# MRCS-8xDPDT-Relay_v1_1.net
KiCad netlist of a schematic drawn in EAGLE
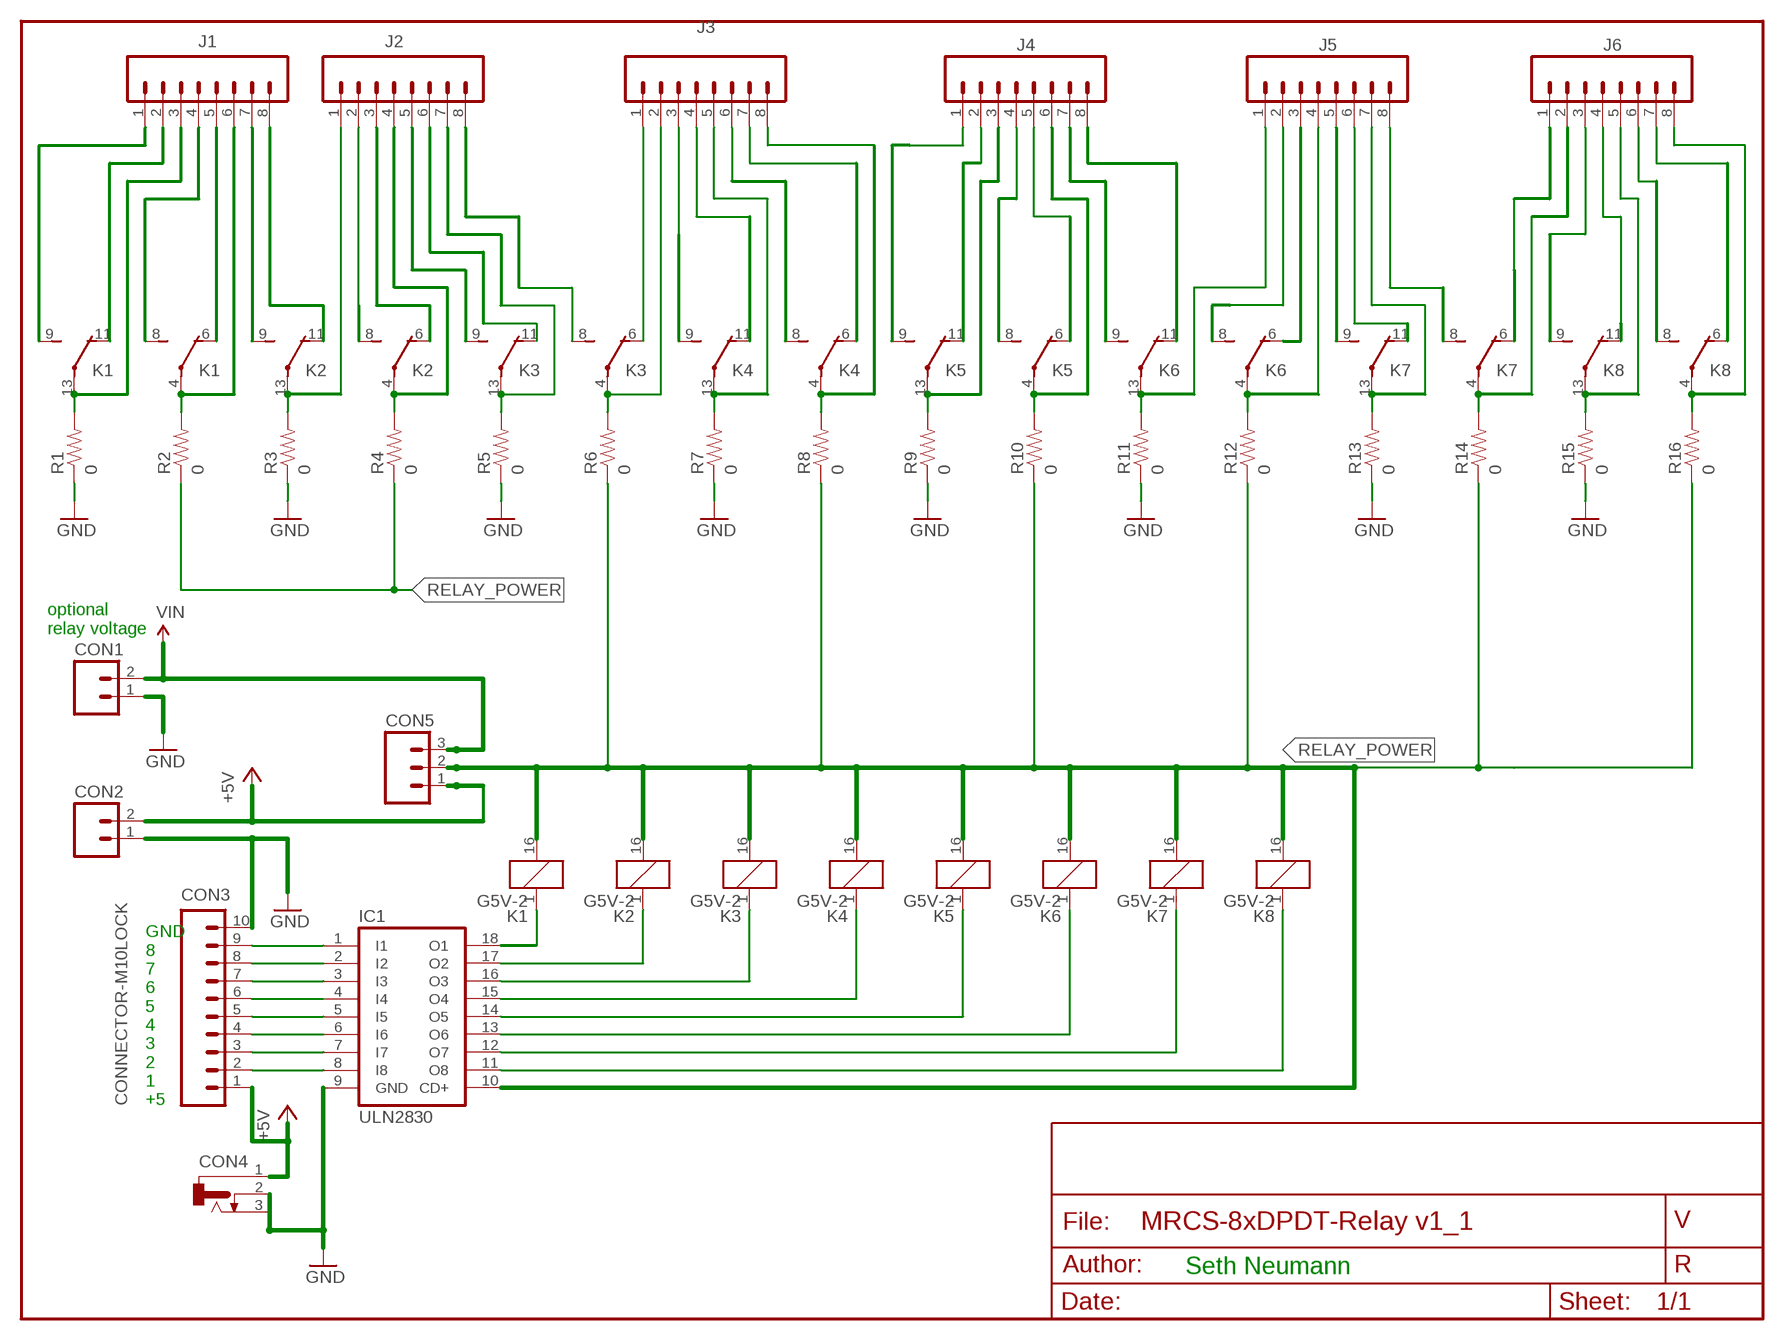
[diagram p0: schematic, sheet 1]

(export (version "E")
  (design (tool "Eeschema 10.0.6"))
  (components
    (comp (ref "CON1")
      (value "CONNECTOR-M023.5MM-LOCK")
      (footprint "eagle-import:SCREWTERMINAL-3.5MM-2_LOCK")
      (libsource (lib "eagle-import") (part "CONNECTOR-M023.5MM-LOCK"))
    )
    (comp (ref "CON2")
      (value "CONNECTOR-M023.5MM-LOCK")
      (footprint "eagle-import:SCREWTERMINAL-3.5MM-2_LOCK")
      (libsource (lib "eagle-import") (part "CONNECTOR-M023.5MM-LOCK"))
    )
    (comp (ref "CON3")
      (value "CONNECTOR-M10LOCK")
      (footprint "eagle-import:1X10_LOCK")
      (libsource (lib "eagle-import") (part "CONNECTOR-M10LOCK"))
    )
    (comp (ref "CON4")
      (value "CONNECTOR-DC-POWER-RA")
      (footprint "eagle-import:DCJ0202")
      (libsource (lib "eagle-import") (part "CONNECTOR-DC-POWER-RA"))
    )
    (comp (ref "CON5")
      (value "CONNECTOR-M03MOLEX-254-LOCK")
      (footprint "eagle-import:MOLEX-1X3_LOCK")
      (libsource (lib "eagle-import") (part "CONNECTOR-M03MOLEX-254-LOCK"))
    )
    (comp (ref "IC1")
      (value "ULN2830")
      (footprint "eagle-import:DIL18")
      (libsource (lib "eagle-import") (part "ULN2803A"))
    )
    (comp (ref "J1")
      (value "CONNECTOR-M08LOCK")
      (footprint "eagle-import:1X08_LOCK")
      (libsource (lib "eagle-import") (part "CONNECTOR-M08LOCK"))
    )
    (comp (ref "J2")
      (value "CONNECTOR-M08LOCK")
      (footprint "eagle-import:1X08_LOCK")
      (libsource (lib "eagle-import") (part "CONNECTOR-M08LOCK"))
    )
    (comp (ref "J3")
      (value "CONNECTOR-M08LOCK")
      (footprint "eagle-import:1X08_LOCK")
      (libsource (lib "eagle-import") (part "CONNECTOR-M08LOCK"))
    )
    (comp (ref "J4")
      (value "CONNECTOR-M08LOCK")
      (footprint "eagle-import:1X08_LOCK")
      (libsource (lib "eagle-import") (part "CONNECTOR-M08LOCK"))
    )
    (comp (ref "J5")
      (value "CONNECTOR-M08LOCK")
      (footprint "eagle-import:1X08_LOCK")
      (libsource (lib "eagle-import") (part "CONNECTOR-M08LOCK"))
    )
    (comp (ref "J6")
      (value "CONNECTOR-M08LOCK")
      (footprint "eagle-import:1X08_LOCK")
      (libsource (lib "eagle-import") (part "CONNECTOR-M08LOCK"))
    )
    (comp (ref "K1")
      (value "G5V-2")
      (footprint "eagle-import:G5V-2")
      (fields (field (name "MPN") "G5V-2 5DC"))
      (libsource (lib "eagle-import") (part "G5V-2"))
    )
    (comp (ref "K2")
      (value "G5V-2")
      (footprint "eagle-import:G5V-2")
      (fields (field (name "MPN") "G5V-2 5DC"))
      (libsource (lib "eagle-import") (part "G5V-2"))
    )
    (comp (ref "K3")
      (value "G5V-2")
      (footprint "eagle-import:G5V-2")
      (fields (field (name "MPN") "G5V-2 5DC"))
      (libsource (lib "eagle-import") (part "G5V-2"))
    )
    (comp (ref "K4")
      (value "G5V-2")
      (footprint "eagle-import:G5V-2")
      (fields (field (name "MPN") "G5V-2 5DC"))
      (libsource (lib "eagle-import") (part "G5V-2"))
    )
    (comp (ref "K5")
      (value "G5V-2")
      (footprint "eagle-import:G5V-2")
      (fields (field (name "MPN") "G5V-2 5DC"))
      (libsource (lib "eagle-import") (part "G5V-2"))
    )
    (comp (ref "K6")
      (value "G5V-2")
      (footprint "eagle-import:G5V-2")
      (fields (field (name "MPN") "G5V-2 5DC"))
      (libsource (lib "eagle-import") (part "G5V-2"))
    )
    (comp (ref "K7")
      (value "G5V-2")
      (footprint "eagle-import:G5V-2")
      (fields (field (name "MPN") "G5V-2 5DC"))
      (libsource (lib "eagle-import") (part "G5V-2"))
    )
    (comp (ref "K8")
      (value "G5V-2")
      (footprint "eagle-import:G5V-2")
      (fields (field (name "MPN") "G5V-2 5DC"))
      (libsource (lib "eagle-import") (part "G5V-2"))
    )
    (comp (ref "R1")
      (value "0")
      (footprint "eagle-import:CUT-R")
      (libsource (lib "eagle-import") (part "RPTH-R0"))
    )
    (comp (ref "R2")
      (value "0")
      (footprint "eagle-import:CUT-R")
      (libsource (lib "eagle-import") (part "RPTH-R0"))
    )
    (comp (ref "R3")
      (value "0")
      (footprint "eagle-import:CUT-R")
      (libsource (lib "eagle-import") (part "RPTH-R0"))
    )
    (comp (ref "R4")
      (value "0")
      (footprint "eagle-import:CUT-R")
      (libsource (lib "eagle-import") (part "RPTH-R0"))
    )
    (comp (ref "R5")
      (value "0")
      (footprint "eagle-import:CUT-R")
      (libsource (lib "eagle-import") (part "RPTH-R0"))
    )
    (comp (ref "R6")
      (value "0")
      (footprint "eagle-import:CUT-R")
      (libsource (lib "eagle-import") (part "RPTH-R0"))
    )
    (comp (ref "R7")
      (value "0")
      (footprint "eagle-import:CUT-R")
      (libsource (lib "eagle-import") (part "RPTH-R0"))
    )
    (comp (ref "R8")
      (value "0")
      (footprint "eagle-import:CUT-R")
      (libsource (lib "eagle-import") (part "RPTH-R0"))
    )
    (comp (ref "R9")
      (value "0")
      (footprint "eagle-import:CUT-R")
      (libsource (lib "eagle-import") (part "RPTH-R0"))
    )
    (comp (ref "R10")
      (value "0")
      (footprint "eagle-import:CUT-R")
      (libsource (lib "eagle-import") (part "RPTH-R0"))
    )
    (comp (ref "R11")
      (value "0")
      (footprint "eagle-import:CUT-R")
      (libsource (lib "eagle-import") (part "RPTH-R0"))
    )
    (comp (ref "R12")
      (value "0")
      (footprint "eagle-import:CUT-R")
      (libsource (lib "eagle-import") (part "RPTH-R0"))
    )
    (comp (ref "R13")
      (value "0")
      (footprint "eagle-import:CUT-R")
      (libsource (lib "eagle-import") (part "RPTH-R0"))
    )
    (comp (ref "R14")
      (value "0")
      (footprint "eagle-import:CUT-R")
      (libsource (lib "eagle-import") (part "RPTH-R0"))
    )
    (comp (ref "R15")
      (value "0")
      (footprint "eagle-import:CUT-R")
      (libsource (lib "eagle-import") (part "RPTH-R0"))
    )
    (comp (ref "R16")
      (value "0")
      (footprint "eagle-import:CUT-R")
      (libsource (lib "eagle-import") (part "RPTH-R0"))
    )
  )
  (nets
    (net (code "1") (name "+5V") (class "Default")
      (node (ref "CON2") (pin "2") (pinfunction "B_2") (pintype "passive"))
      (node (ref "CON3") (pin "1") (pinfunction "1_1") (pintype "passive"))
      (node (ref "CON4") (pin "1") (pinfunction "1_1") (pintype "passive"))
      (node (ref "CON5") (pin "1") (pinfunction "1_1") (pintype "passive"))
    )
    (net (code "2") (name "GND") (class "Default")
      (node (ref "CON1") (pin "1") (pinfunction "A_1") (pintype "passive"))
      (node (ref "CON2") (pin "1") (pinfunction "A_1") (pintype "passive"))
      (node (ref "CON3") (pin "10") (pinfunction "10_10") (pintype "passive"))
      (node (ref "CON4") (pin "2") (pinfunction "2_2") (pintype "passive"))
      (node (ref "CON4") (pin "3") (pinfunction "3_3") (pintype "passive"))
      (node (ref "IC1") (pin "9") (pinfunction "GND_9") (pintype "power_in"))
      (node (ref "R1") (pin "P2") (pinfunction "1_P2") (pintype "passive"))
      (node (ref "R11") (pin "P2") (pinfunction "1_P2") (pintype "passive"))
      (node (ref "R13") (pin "P2") (pinfunction "1_P2") (pintype "passive"))
      (node (ref "R15") (pin "P2") (pinfunction "1_P2") (pintype "passive"))
      (node (ref "R3") (pin "P2") (pinfunction "1_P2") (pintype "passive"))
      (node (ref "R5") (pin "P2") (pinfunction "1_P2") (pintype "passive"))
      (node (ref "R7") (pin "P2") (pinfunction "1_P2") (pintype "passive"))
      (node (ref "R9") (pin "P2") (pinfunction "1_P2") (pintype "passive"))
    )
    (net (code "3") (name "Net-(IC1-I1)") (class "Default")
      (node (ref "CON3") (pin "9") (pinfunction "9_9") (pintype "passive"))
      (node (ref "IC1") (pin "1") (pinfunction "I1_1") (pintype "input"))
    )
    (net (code "4") (name "Net-(IC1-I2)") (class "Default")
      (node (ref "CON3") (pin "8") (pinfunction "8_8") (pintype "passive"))
      (node (ref "IC1") (pin "2") (pinfunction "I2_2") (pintype "input"))
    )
    (net (code "5") (name "Net-(IC1-I3)") (class "Default")
      (node (ref "CON3") (pin "7") (pinfunction "7_7") (pintype "passive"))
      (node (ref "IC1") (pin "3") (pinfunction "I3_3") (pintype "input"))
    )
    (net (code "6") (name "Net-(IC1-I4)") (class "Default")
      (node (ref "CON3") (pin "6") (pinfunction "6_6") (pintype "passive"))
      (node (ref "IC1") (pin "4") (pinfunction "I4_4") (pintype "input"))
    )
    (net (code "7") (name "Net-(IC1-I5)") (class "Default")
      (node (ref "CON3") (pin "5") (pinfunction "5_5") (pintype "passive"))
      (node (ref "IC1") (pin "5") (pinfunction "I5_5") (pintype "input"))
    )
    (net (code "8") (name "Net-(IC1-I6)") (class "Default")
      (node (ref "CON3") (pin "4") (pinfunction "4_4") (pintype "passive"))
      (node (ref "IC1") (pin "6") (pinfunction "I6_6") (pintype "input"))
    )
    (net (code "9") (name "Net-(IC1-I7)") (class "Default")
      (node (ref "CON3") (pin "3") (pinfunction "3_3") (pintype "passive"))
      (node (ref "IC1") (pin "7") (pinfunction "I7_7") (pintype "input"))
    )
    (net (code "10") (name "Net-(IC1-I8)") (class "Default")
      (node (ref "CON3") (pin "2") (pinfunction "2_2") (pintype "passive"))
      (node (ref "IC1") (pin "8") (pinfunction "I8_8") (pintype "input"))
    )
    (net (code "11") (name "Net-(IC1-O1)") (class "Default")
      (node (ref "IC1") (pin "18") (pinfunction "O1_18") (pintype "open_collector"))
      (node (ref "K1") (pin "1") (pinfunction "1_1") (pintype "passive"))
    )
    (net (code "12") (name "Net-(IC1-O2)") (class "Default")
      (node (ref "IC1") (pin "17") (pinfunction "O2_17") (pintype "open_collector"))
      (node (ref "K2") (pin "1") (pinfunction "1_1") (pintype "passive"))
    )
    (net (code "13") (name "Net-(IC1-O3)") (class "Default")
      (node (ref "IC1") (pin "16") (pinfunction "O3_16") (pintype "open_collector"))
      (node (ref "K3") (pin "1") (pinfunction "1_1") (pintype "passive"))
    )
    (net (code "14") (name "Net-(IC1-O4)") (class "Default")
      (node (ref "IC1") (pin "15") (pinfunction "O4_15") (pintype "open_collector"))
      (node (ref "K4") (pin "1") (pinfunction "1_1") (pintype "passive"))
    )
    (net (code "15") (name "Net-(IC1-O5)") (class "Default")
      (node (ref "IC1") (pin "14") (pinfunction "O5_14") (pintype "open_collector"))
      (node (ref "K5") (pin "1") (pinfunction "1_1") (pintype "passive"))
    )
    (net (code "16") (name "Net-(IC1-O6)") (class "Default")
      (node (ref "IC1") (pin "13") (pinfunction "O6_13") (pintype "open_collector"))
      (node (ref "K6") (pin "1") (pinfunction "1_1") (pintype "passive"))
    )
    (net (code "17") (name "Net-(IC1-O7)") (class "Default")
      (node (ref "IC1") (pin "12") (pinfunction "O7_12") (pintype "open_collector"))
      (node (ref "K7") (pin "1") (pinfunction "1_1") (pintype "passive"))
    )
    (net (code "18") (name "Net-(IC1-O8)") (class "Default")
      (node (ref "IC1") (pin "11") (pinfunction "O8_11") (pintype "open_collector"))
      (node (ref "K8") (pin "1") (pinfunction "1_1") (pintype "passive"))
    )
    (net (code "19") (name "Net-(K1A-O)") (class "Default")
      (node (ref "J1") (pin "5") (pinfunction "5_5") (pintype "passive"))
      (node (ref "K1") (pin "6") (pinfunction "O_6") (pintype "passive"))
    )
    (net (code "20") (name "Net-(K1A-P)") (class "Default")
      (node (ref "J1") (pin "6") (pinfunction "6_6") (pintype "passive"))
      (node (ref "K1") (pin "4") (pinfunction "P_4") (pintype "passive"))
      (node (ref "R2") (pin "P1") (pinfunction "2_P1") (pintype "passive"))
    )
    (net (code "21") (name "Net-(K1A-S)") (class "Default")
      (node (ref "J1") (pin "4") (pinfunction "4_4") (pintype "passive"))
      (node (ref "K1") (pin "8") (pinfunction "S_8") (pintype "passive"))
    )
    (net (code "22") (name "Net-(K1B-O)") (class "Default")
      (node (ref "J1") (pin "2") (pinfunction "2_2") (pintype "passive"))
      (node (ref "K1") (pin "11") (pinfunction "O_11") (pintype "passive"))
    )
    (net (code "23") (name "Net-(K1B-P)") (class "Default")
      (node (ref "J1") (pin "3") (pinfunction "3_3") (pintype "passive"))
      (node (ref "K1") (pin "13") (pinfunction "P_13") (pintype "passive"))
      (node (ref "R1") (pin "P1") (pinfunction "2_P1") (pintype "passive"))
    )
    (net (code "24") (name "Net-(K1B-S)") (class "Default")
      (node (ref "J1") (pin "1") (pinfunction "1_1") (pintype "passive"))
      (node (ref "K1") (pin "9") (pinfunction "S_9") (pintype "passive"))
    )
    (net (code "25") (name "Net-(K2A-O)") (class "Default")
      (node (ref "J2") (pin "3") (pinfunction "3_3") (pintype "passive"))
      (node (ref "K2") (pin "6") (pinfunction "O_6") (pintype "passive"))
    )
    (net (code "26") (name "Net-(K2A-P)") (class "Default")
      (node (ref "J2") (pin "4") (pinfunction "4_4") (pintype "passive"))
      (node (ref "K2") (pin "4") (pinfunction "P_4") (pintype "passive"))
      (node (ref "R4") (pin "P1") (pinfunction "2_P1") (pintype "passive"))
    )
    (net (code "27") (name "Net-(K2A-S)") (class "Default")
      (node (ref "J2") (pin "2") (pinfunction "2_2") (pintype "passive"))
      (node (ref "K2") (pin "8") (pinfunction "S_8") (pintype "passive"))
    )
    (net (code "28") (name "Net-(K2B-O)") (class "Default")
      (node (ref "J1") (pin "8") (pinfunction "8_8") (pintype "passive"))
      (node (ref "K2") (pin "11") (pinfunction "O_11") (pintype "passive"))
    )
    (net (code "29") (name "Net-(K2B-P)") (class "Default")
      (node (ref "J2") (pin "1") (pinfunction "1_1") (pintype "passive"))
      (node (ref "K2") (pin "13") (pinfunction "P_13") (pintype "passive"))
      (node (ref "R3") (pin "P1") (pinfunction "2_P1") (pintype "passive"))
    )
    (net (code "30") (name "Net-(K2B-S)") (class "Default")
      (node (ref "J1") (pin "7") (pinfunction "7_7") (pintype "passive"))
      (node (ref "K2") (pin "9") (pinfunction "S_9") (pintype "passive"))
    )
    (net (code "31") (name "Net-(K3A-O)") (class "Default")
      (node (ref "J3") (pin "1") (pinfunction "1_1") (pintype "passive"))
      (node (ref "K3") (pin "6") (pinfunction "O_6") (pintype "passive"))
    )
    (net (code "32") (name "Net-(K3A-P)") (class "Default")
      (node (ref "J3") (pin "2") (pinfunction "2_2") (pintype "passive"))
      (node (ref "K3") (pin "4") (pinfunction "P_4") (pintype "passive"))
      (node (ref "R6") (pin "P1") (pinfunction "2_P1") (pintype "passive"))
    )
    (net (code "33") (name "Net-(K3A-S)") (class "Default")
      (node (ref "J2") (pin "8") (pinfunction "8_8") (pintype "passive"))
      (node (ref "K3") (pin "8") (pinfunction "S_8") (pintype "passive"))
    )
    (net (code "34") (name "Net-(K3B-O)") (class "Default")
      (node (ref "J2") (pin "6") (pinfunction "6_6") (pintype "passive"))
      (node (ref "K3") (pin "11") (pinfunction "O_11") (pintype "passive"))
    )
    (net (code "35") (name "Net-(K3B-P)") (class "Default")
      (node (ref "J2") (pin "7") (pinfunction "7_7") (pintype "passive"))
      (node (ref "K3") (pin "13") (pinfunction "P_13") (pintype "passive"))
      (node (ref "R5") (pin "P1") (pinfunction "2_P1") (pintype "passive"))
    )
    (net (code "36") (name "Net-(K3B-S)") (class "Default")
      (node (ref "J2") (pin "5") (pinfunction "5_5") (pintype "passive"))
      (node (ref "K3") (pin "9") (pinfunction "S_9") (pintype "passive"))
    )
    (net (code "37") (name "Net-(K4A-O)") (class "Default")
      (node (ref "J3") (pin "7") (pinfunction "7_7") (pintype "passive"))
      (node (ref "K4") (pin "6") (pinfunction "O_6") (pintype "passive"))
    )
    (net (code "38") (name "Net-(K4A-P)") (class "Default")
      (node (ref "J3") (pin "8") (pinfunction "8_8") (pintype "passive"))
      (node (ref "K4") (pin "4") (pinfunction "P_4") (pintype "passive"))
      (node (ref "R8") (pin "P1") (pinfunction "2_P1") (pintype "passive"))
    )
    (net (code "39") (name "Net-(K4A-S)") (class "Default")
      (node (ref "J3") (pin "6") (pinfunction "6_6") (pintype "passive"))
      (node (ref "K4") (pin "8") (pinfunction "S_8") (pintype "passive"))
    )
    (net (code "40") (name "Net-(K4B-O)") (class "Default")
      (node (ref "J3") (pin "4") (pinfunction "4_4") (pintype "passive"))
      (node (ref "K4") (pin "11") (pinfunction "O_11") (pintype "passive"))
    )
    (net (code "41") (name "Net-(K4B-P)") (class "Default")
      (node (ref "J3") (pin "5") (pinfunction "5_5") (pintype "passive"))
      (node (ref "K4") (pin "13") (pinfunction "P_13") (pintype "passive"))
      (node (ref "R7") (pin "P1") (pinfunction "2_P1") (pintype "passive"))
    )
    (net (code "42") (name "Net-(K4B-S)") (class "Default")
      (node (ref "J3") (pin "3") (pinfunction "3_3") (pintype "passive"))
      (node (ref "K4") (pin "9") (pinfunction "S_9") (pintype "passive"))
    )
    (net (code "43") (name "Net-(K5A-O)") (class "Default")
      (node (ref "J4") (pin "5") (pinfunction "5_5") (pintype "passive"))
      (node (ref "K5") (pin "6") (pinfunction "O_6") (pintype "passive"))
    )
    (net (code "44") (name "Net-(K5A-P)") (class "Default")
      (node (ref "J4") (pin "6") (pinfunction "6_6") (pintype "passive"))
      (node (ref "K5") (pin "4") (pinfunction "P_4") (pintype "passive"))
      (node (ref "R10") (pin "P1") (pinfunction "2_P1") (pintype "passive"))
    )
    (net (code "45") (name "Net-(K5A-S)") (class "Default")
      (node (ref "J4") (pin "4") (pinfunction "4_4") (pintype "passive"))
      (node (ref "K5") (pin "8") (pinfunction "S_8") (pintype "passive"))
    )
    (net (code "46") (name "Net-(K5B-O)") (class "Default")
      (node (ref "J4") (pin "2") (pinfunction "2_2") (pintype "passive"))
      (node (ref "K5") (pin "11") (pinfunction "O_11") (pintype "passive"))
    )
    (net (code "47") (name "Net-(K5B-P)") (class "Default")
      (node (ref "J4") (pin "3") (pinfunction "3_3") (pintype "passive"))
      (node (ref "K5") (pin "13") (pinfunction "P_13") (pintype "passive"))
      (node (ref "R9") (pin "P1") (pinfunction "2_P1") (pintype "passive"))
    )
    (net (code "48") (name "Net-(K5B-S)") (class "Default")
      (node (ref "J4") (pin "1") (pinfunction "1_1") (pintype "passive"))
      (node (ref "K5") (pin "9") (pinfunction "S_9") (pintype "passive"))
    )
    (net (code "49") (name "Net-(K6A-O)") (class "Default")
      (node (ref "J5") (pin "3") (pinfunction "3_3") (pintype "passive"))
      (node (ref "K6") (pin "6") (pinfunction "O_6") (pintype "passive"))
    )
    (net (code "50") (name "Net-(K6A-P)") (class "Default")
      (node (ref "J5") (pin "4") (pinfunction "4_4") (pintype "passive"))
      (node (ref "K6") (pin "4") (pinfunction "P_4") (pintype "passive"))
      (node (ref "R12") (pin "P1") (pinfunction "2_P1") (pintype "passive"))
    )
    (net (code "51") (name "Net-(K6A-S)") (class "Default")
      (node (ref "J5") (pin "2") (pinfunction "2_2") (pintype "passive"))
      (node (ref "K6") (pin "8") (pinfunction "S_8") (pintype "passive"))
    )
    (net (code "52") (name "Net-(K6B-O)") (class "Default")
      (node (ref "J4") (pin "8") (pinfunction "8_8") (pintype "passive"))
      (node (ref "K6") (pin "11") (pinfunction "O_11") (pintype "passive"))
    )
    (net (code "53") (name "Net-(K6B-P)") (class "Default")
      (node (ref "J5") (pin "1") (pinfunction "1_1") (pintype "passive"))
      (node (ref "K6") (pin "13") (pinfunction "P_13") (pintype "passive"))
      (node (ref "R11") (pin "P1") (pinfunction "2_P1") (pintype "passive"))
    )
    (net (code "54") (name "Net-(K6B-S)") (class "Default")
      (node (ref "J4") (pin "7") (pinfunction "7_7") (pintype "passive"))
      (node (ref "K6") (pin "9") (pinfunction "S_9") (pintype "passive"))
    )
    (net (code "55") (name "Net-(K7A-O)") (class "Default")
      (node (ref "J6") (pin "1") (pinfunction "1_1") (pintype "passive"))
      (node (ref "K7") (pin "6") (pinfunction "O_6") (pintype "passive"))
    )
    (net (code "56") (name "Net-(K7A-P)") (class "Default")
      (node (ref "J6") (pin "2") (pinfunction "2_2") (pintype "passive"))
      (node (ref "K7") (pin "4") (pinfunction "P_4") (pintype "passive"))
      (node (ref "R14") (pin "P1") (pinfunction "2_P1") (pintype "passive"))
    )
    (net (code "57") (name "Net-(K7A-S)") (class "Default")
      (node (ref "J5") (pin "8") (pinfunction "8_8") (pintype "passive"))
      (node (ref "K7") (pin "8") (pinfunction "S_8") (pintype "passive"))
    )
    (net (code "58") (name "Net-(K7B-O)") (class "Default")
      (node (ref "J5") (pin "6") (pinfunction "6_6") (pintype "passive"))
      (node (ref "K7") (pin "11") (pinfunction "O_11") (pintype "passive"))
    )
    (net (code "59") (name "Net-(K7B-P)") (class "Default")
      (node (ref "J5") (pin "7") (pinfunction "7_7") (pintype "passive"))
      (node (ref "K7") (pin "13") (pinfunction "P_13") (pintype "passive"))
      (node (ref "R13") (pin "P1") (pinfunction "2_P1") (pintype "passive"))
    )
    (net (code "60") (name "Net-(K7B-S)") (class "Default")
      (node (ref "J5") (pin "5") (pinfunction "5_5") (pintype "passive"))
      (node (ref "K7") (pin "9") (pinfunction "S_9") (pintype "passive"))
    )
    (net (code "61") (name "Net-(K8A-O)") (class "Default")
      (node (ref "J6") (pin "7") (pinfunction "7_7") (pintype "passive"))
      (node (ref "K8") (pin "6") (pinfunction "O_6") (pintype "passive"))
    )
    (net (code "62") (name "Net-(K8A-P)") (class "Default")
      (node (ref "J6") (pin "8") (pinfunction "8_8") (pintype "passive"))
      (node (ref "K8") (pin "4") (pinfunction "P_4") (pintype "passive"))
      (node (ref "R16") (pin "P1") (pinfunction "2_P1") (pintype "passive"))
    )
    (net (code "63") (name "Net-(K8A-S)") (class "Default")
      (node (ref "J6") (pin "6") (pinfunction "6_6") (pintype "passive"))
      (node (ref "K8") (pin "8") (pinfunction "S_8") (pintype "passive"))
    )
    (net (code "64") (name "Net-(K8B-O)") (class "Default")
      (node (ref "J6") (pin "4") (pinfunction "4_4") (pintype "passive"))
      (node (ref "K8") (pin "11") (pinfunction "O_11") (pintype "passive"))
    )
    (net (code "65") (name "Net-(K8B-P)") (class "Default")
      (node (ref "J6") (pin "5") (pinfunction "5_5") (pintype "passive"))
      (node (ref "K8") (pin "13") (pinfunction "P_13") (pintype "passive"))
      (node (ref "R15") (pin "P1") (pinfunction "2_P1") (pintype "passive"))
    )
    (net (code "66") (name "Net-(K8B-S)") (class "Default")
      (node (ref "J6") (pin "3") (pinfunction "3_3") (pintype "passive"))
      (node (ref "K8") (pin "9") (pinfunction "S_9") (pintype "passive"))
    )
    (net (code "67") (name "RELAY_POWER") (class "Default")
      (node (ref "CON5") (pin "2") (pinfunction "2_2") (pintype "passive"))
      (node (ref "IC1") (pin "10") (pinfunction "CD+_10") (pintype "passive"))
      (node (ref "K1") (pin "16") (pinfunction "2_16") (pintype "passive"))
      (node (ref "K2") (pin "16") (pinfunction "2_16") (pintype "passive"))
      (node (ref "K3") (pin "16") (pinfunction "2_16") (pintype "passive"))
      (node (ref "K4") (pin "16") (pinfunction "2_16") (pintype "passive"))
      (node (ref "K5") (pin "16") (pinfunction "2_16") (pintype "passive"))
      (node (ref "K6") (pin "16") (pinfunction "2_16") (pintype "passive"))
      (node (ref "K7") (pin "16") (pinfunction "2_16") (pintype "passive"))
      (node (ref "K8") (pin "16") (pinfunction "2_16") (pintype "passive"))
      (node (ref "R10") (pin "P2") (pinfunction "1_P2") (pintype "passive"))
      (node (ref "R12") (pin "P2") (pinfunction "1_P2") (pintype "passive"))
      (node (ref "R14") (pin "P2") (pinfunction "1_P2") (pintype "passive"))
      (node (ref "R16") (pin "P2") (pinfunction "1_P2") (pintype "passive"))
      (node (ref "R2") (pin "P2") (pinfunction "1_P2") (pintype "passive"))
      (node (ref "R4") (pin "P2") (pinfunction "1_P2") (pintype "passive"))
      (node (ref "R6") (pin "P2") (pinfunction "1_P2") (pintype "passive"))
      (node (ref "R8") (pin "P2") (pinfunction "1_P2") (pintype "passive"))
    )
    (net (code "68") (name "VIN") (class "Default")
      (node (ref "CON1") (pin "2") (pinfunction "B_2") (pintype "passive"))
      (node (ref "CON5") (pin "3") (pinfunction "3_3") (pintype "passive"))
    )
  )
)
